# BA2PogoBed.net
KiCad netlist of a schematic drawn in EAGLE
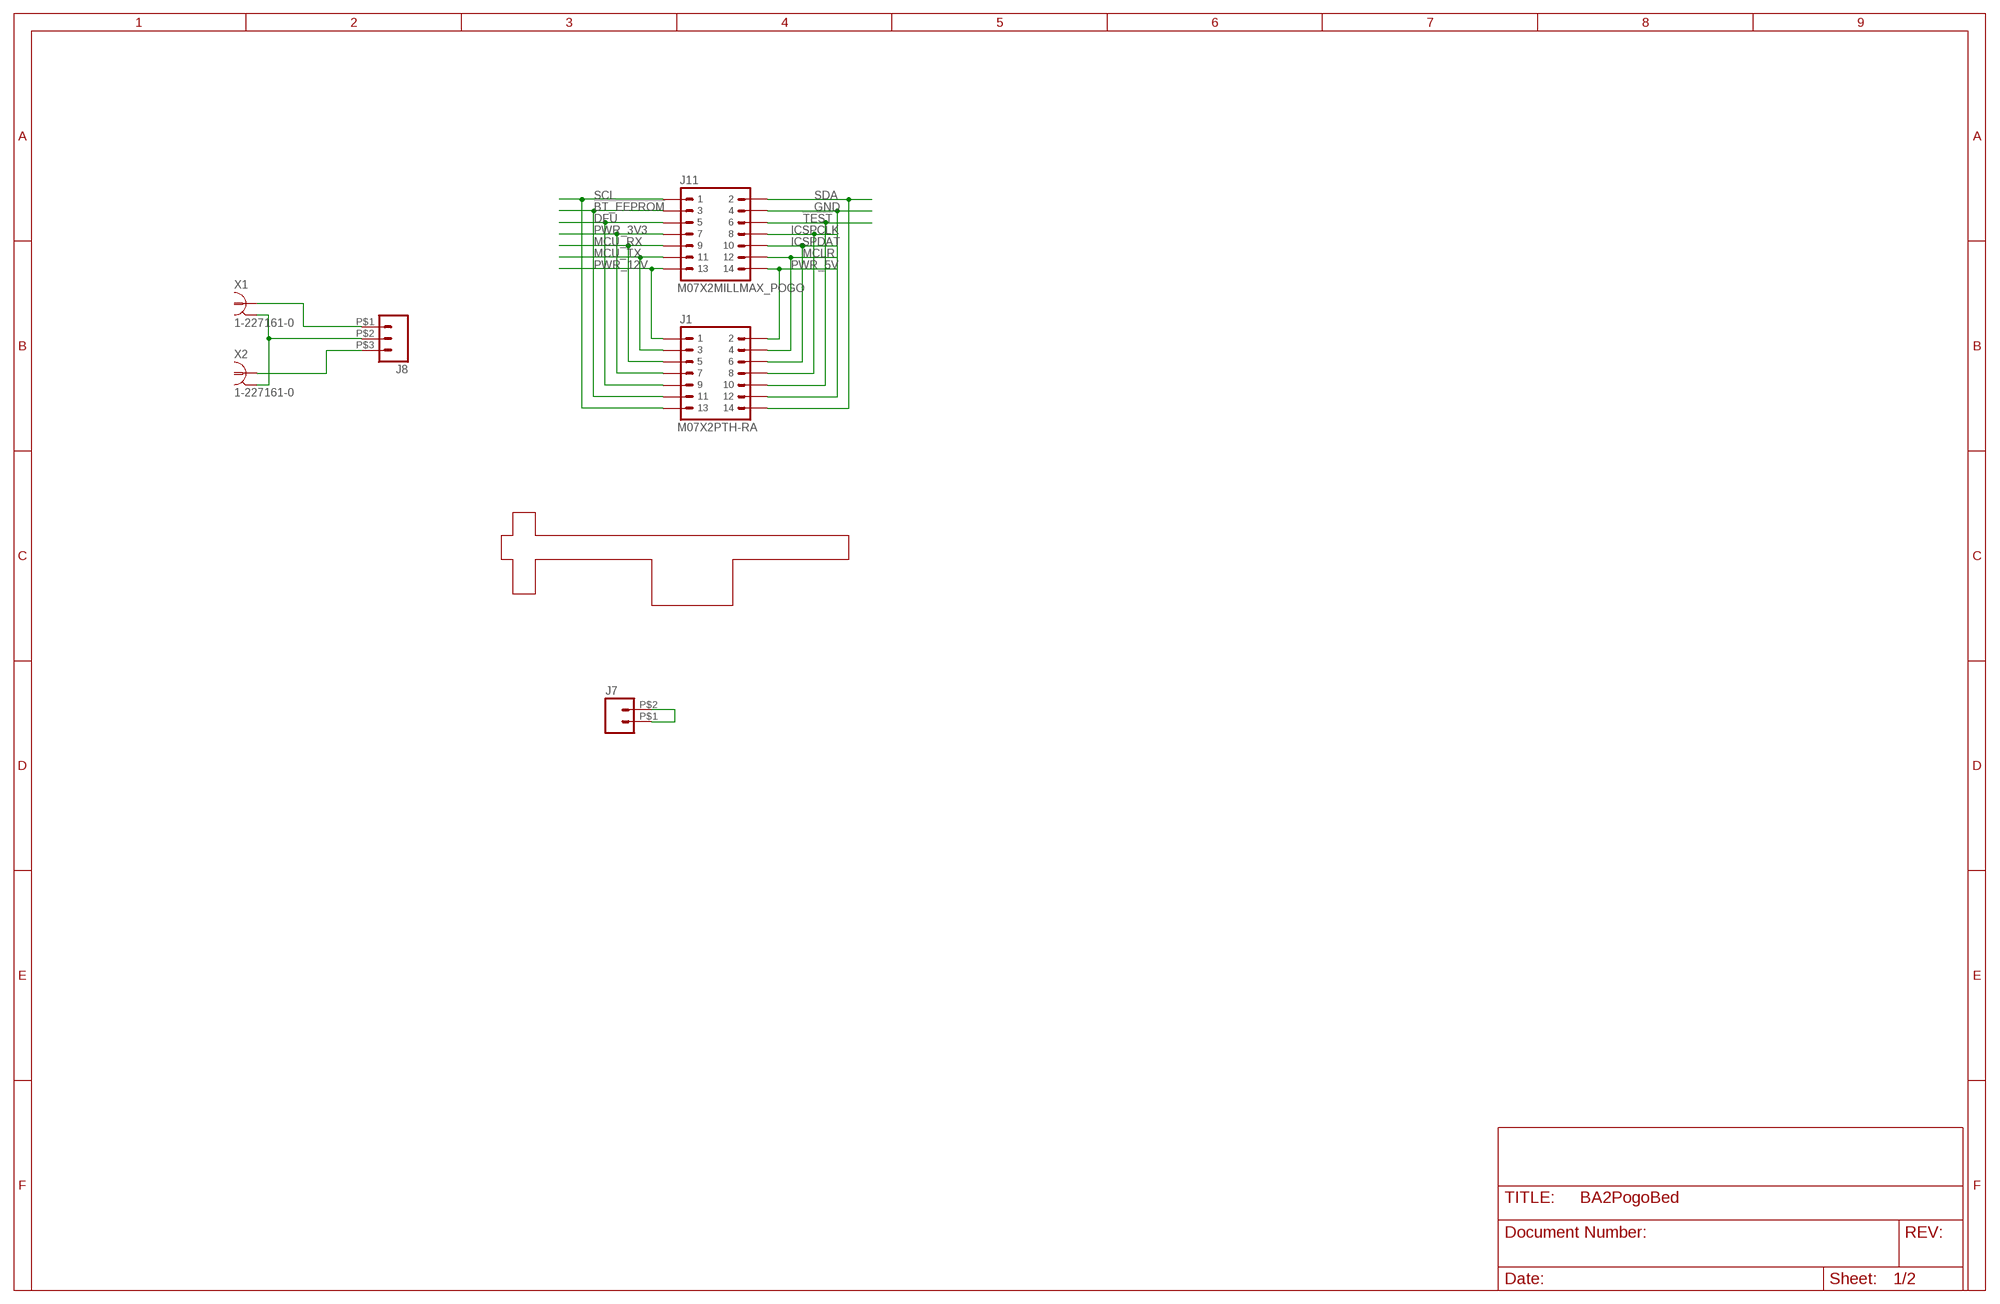
[diagram p0: schematic, sheet 1]

(export (version "E")
  (design (tool "Eeschema 10.0.6"))
  (components
    (comp (ref "J1")
      (value "M07X2PTH-RA")
      (footprint "eagle-import:JST-14-PUD-PTH")
      (libsource (lib "eagle-import") (part "M07X2PTH-RA"))
    )
    (comp (ref "J7")
      (value "M02")
      (footprint "eagle-import:MILLMAX_838_1X2")
      (libsource (lib "eagle-import") (part "M02"))
    )
    (comp (ref "J8")
      (value "M03")
      (footprint "eagle-import:MILLMAX_836_1X3")
      (libsource (lib "eagle-import") (part "M03"))
    )
    (comp (ref "J11")
      (value "M07X2MILLMAX_POGO")
      (footprint "eagle-import:MILLMAX_838_7X2")
      (libsource (lib "eagle-import") (part "M07X2MILLMAX_POGO"))
    )
    (comp (ref "M1")
      (value "TOGGLE_CLAMP_LARGE")
      (footprint "eagle-import:TOGGLE_CLAMP_LARGE")
      (libsource (lib "eagle-import") (part "TOGGLE_CLAMP_LARGE"))
    )
    (comp (ref "X1")
      (value "1-227161-0")
      (footprint "eagle-import:AMP_227161")
      (fields (field (name "MF") "TYCO ELECTRONICS") (field (name "MPN") "1-227161"))
      (libsource (lib "eagle-import") (part "?2271611--0"))
    )
    (comp (ref "X2")
      (value "1-227161-0")
      (footprint "eagle-import:AMP_227161")
      (fields (field (name "MF") "TYCO ELECTRONICS") (field (name "MPN") "1-227161"))
      (libsource (lib "eagle-import") (part "?2271611--0"))
    )
  )
  (nets
    (net (code "1") (name "DFU") (class "Default")
      (node (ref "J1") (pin "P$9") (pinfunction "9_P$9") (pintype "passive"))
      (node (ref "J11") (pin "P$5") (pinfunction "5_P$5") (pintype "passive"))
    )
    (net (code "2") (name "GND") (class "Default")
      (node (ref "J1") (pin "P$12") (pinfunction "12_P$12") (pintype "passive"))
      (node (ref "J11") (pin "P$4") (pinfunction "4_P$4") (pintype "passive"))
    )
    (net (code "3") (name "ICSPCLK") (class "Default")
      (node (ref "J1") (pin "P$8") (pinfunction "8_P$8") (pintype "passive"))
      (node (ref "J11") (pin "P$8") (pinfunction "8_P$8") (pintype "passive"))
    )
    (net (code "4") (name "ICSPDAT") (class "Default")
      (node (ref "J1") (pin "P$6") (pinfunction "6_P$6") (pintype "passive"))
      (node (ref "J11") (pin "P$10") (pinfunction "10_P$10") (pintype "passive"))
    )
    (net (code "5") (name "MCLR") (class "Default")
      (node (ref "J1") (pin "P$4") (pinfunction "4_P$4") (pintype "passive"))
      (node (ref "J11") (pin "P$12") (pinfunction "12_P$12") (pintype "passive"))
    )
    (net (code "6") (name "MCU_RX") (class "Default")
      (node (ref "J1") (pin "P$5") (pinfunction "5_P$5") (pintype "passive"))
      (node (ref "J11") (pin "P$9") (pinfunction "9_P$9") (pintype "passive"))
    )
    (net (code "7") (name "MCU_TX") (class "Default")
      (node (ref "J1") (pin "P$3") (pinfunction "3_P$3") (pintype "passive"))
      (node (ref "J11") (pin "P$11") (pinfunction "11_P$11") (pintype "passive"))
    )
    (net (code "8") (name "Net-(J7-1)") (class "Default")
      (node (ref "J7") (pin "P$1") (pinfunction "1_P$1") (pintype "passive"))
      (node (ref "J7") (pin "P$2") (pinfunction "2_P$2") (pintype "passive"))
    )
    (net (code "9") (name "Net-(J8-1)") (class "Default")
      (node (ref "J8") (pin "P$1") (pinfunction "1_P$1") (pintype "passive"))
      (node (ref "X1") (pin "1") (pinfunction "1_1") (pintype "passive"))
    )
    (net (code "10") (name "Net-(J8-2)") (class "Default")
      (node (ref "J8") (pin "P$2") (pinfunction "2_P$2") (pintype "passive"))
      (node (ref "X1") (pin "2") (pinfunction "2_2") (pintype "passive"))
      (node (ref "X2") (pin "2") (pinfunction "2_2") (pintype "passive"))
    )
    (net (code "11") (name "Net-(J8-3)") (class "Default")
      (node (ref "J8") (pin "P$3") (pinfunction "3_P$3") (pintype "passive"))
      (node (ref "X2") (pin "1") (pinfunction "1_1") (pintype "passive"))
    )
    (net (code "12") (name "PWR_3V3") (class "Default")
      (node (ref "J1") (pin "P$7") (pinfunction "7_P$7") (pintype "passive"))
      (node (ref "J11") (pin "P$7") (pinfunction "7_P$7") (pintype "passive"))
    )
    (net (code "13") (name "PWR_5V") (class "Default")
      (node (ref "J1") (pin "P$2") (pinfunction "2_P$2") (pintype "passive"))
      (node (ref "J11") (pin "P$14") (pinfunction "14_P$14") (pintype "passive"))
    )
    (net (code "14") (name "PWR_12V") (class "Default")
      (node (ref "J1") (pin "P$1") (pinfunction "1_P$1") (pintype "passive"))
      (node (ref "J11") (pin "P$13") (pinfunction "13_P$13") (pintype "passive"))
    )
    (net (code "15") (name "SCL") (class "Default")
      (node (ref "J1") (pin "P$13") (pinfunction "13_P$13") (pintype "passive"))
      (node (ref "J11") (pin "P$1") (pinfunction "1_P$1") (pintype "passive"))
    )
    (net (code "16") (name "SDA") (class "Default")
      (node (ref "J1") (pin "P$14") (pinfunction "14_P$14") (pintype "passive"))
      (node (ref "J11") (pin "P$2") (pinfunction "2_P$2") (pintype "passive"))
    )
    (net (code "17") (name "~{BT_EEPROM}") (class "Default")
      (node (ref "J1") (pin "P$11") (pinfunction "11_P$11") (pintype "passive"))
      (node (ref "J11") (pin "P$3") (pinfunction "3_P$3") (pintype "passive"))
    )
    (net (code "18") (name "~{TEST}") (class "Default")
      (node (ref "J1") (pin "P$10") (pinfunction "10_P$10") (pintype "passive"))
      (node (ref "J11") (pin "P$6") (pinfunction "6_P$6") (pintype "passive"))
    )
  )
)
